# 10MHzRefOsc_2V1.net
KiCad netlist of a schematic drawn in EAGLE
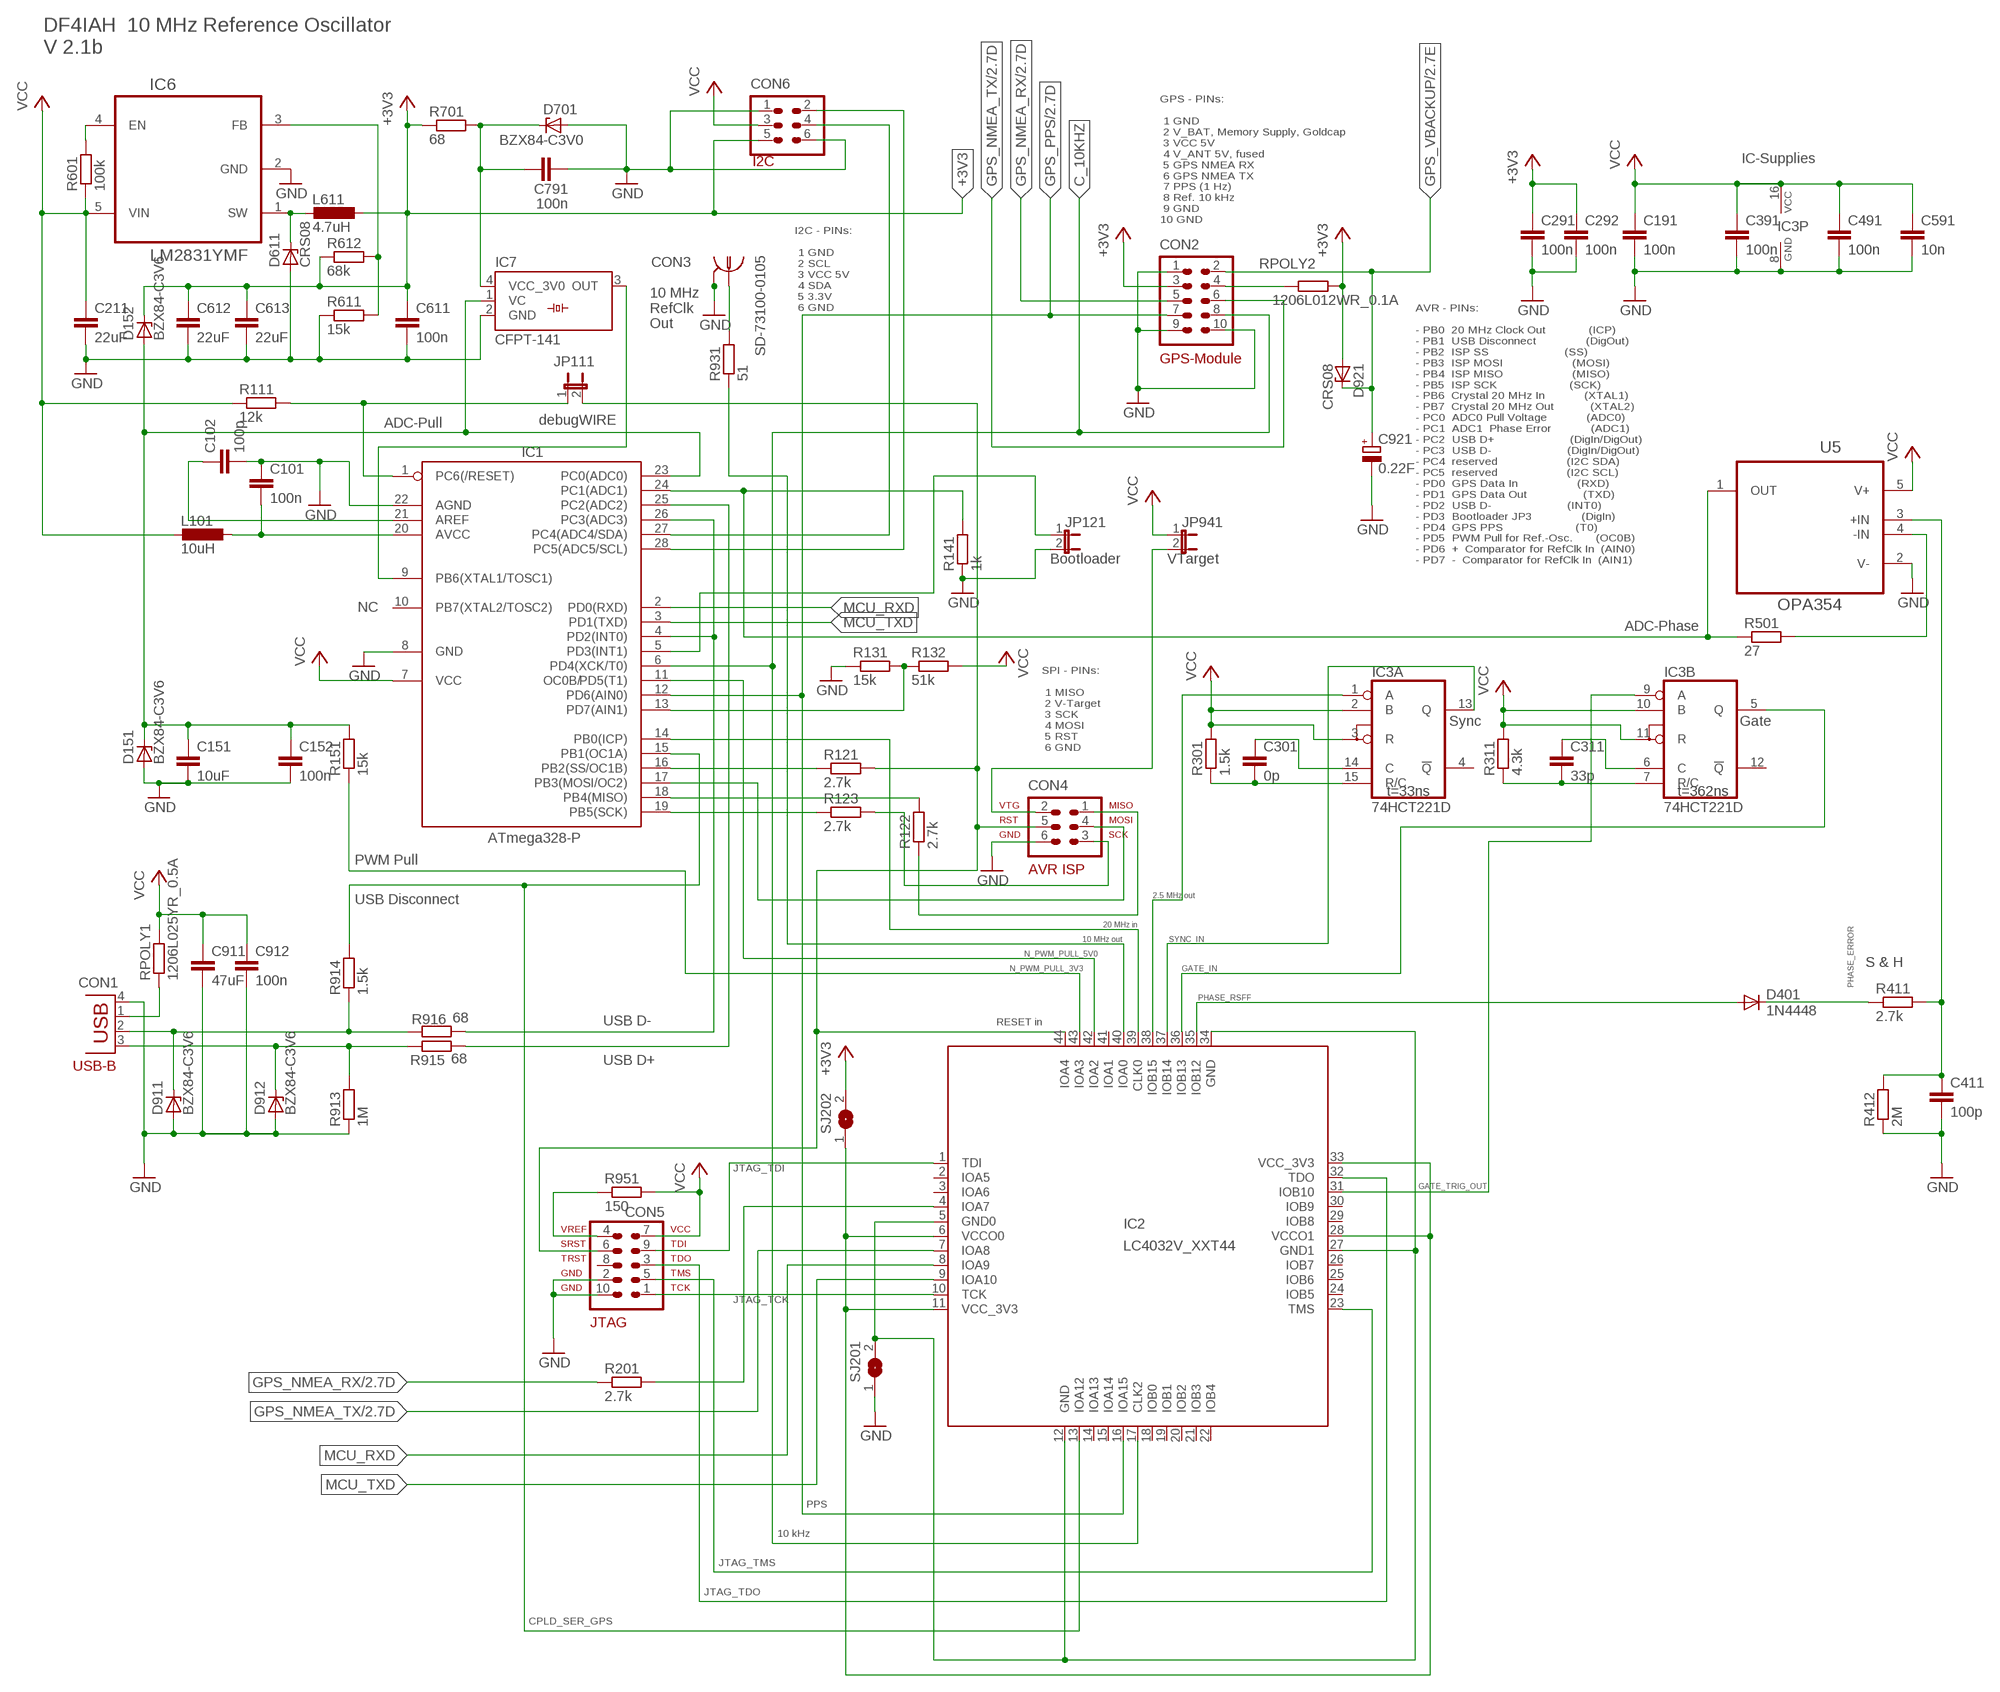
[diagram p0: schematic, sheet 1]
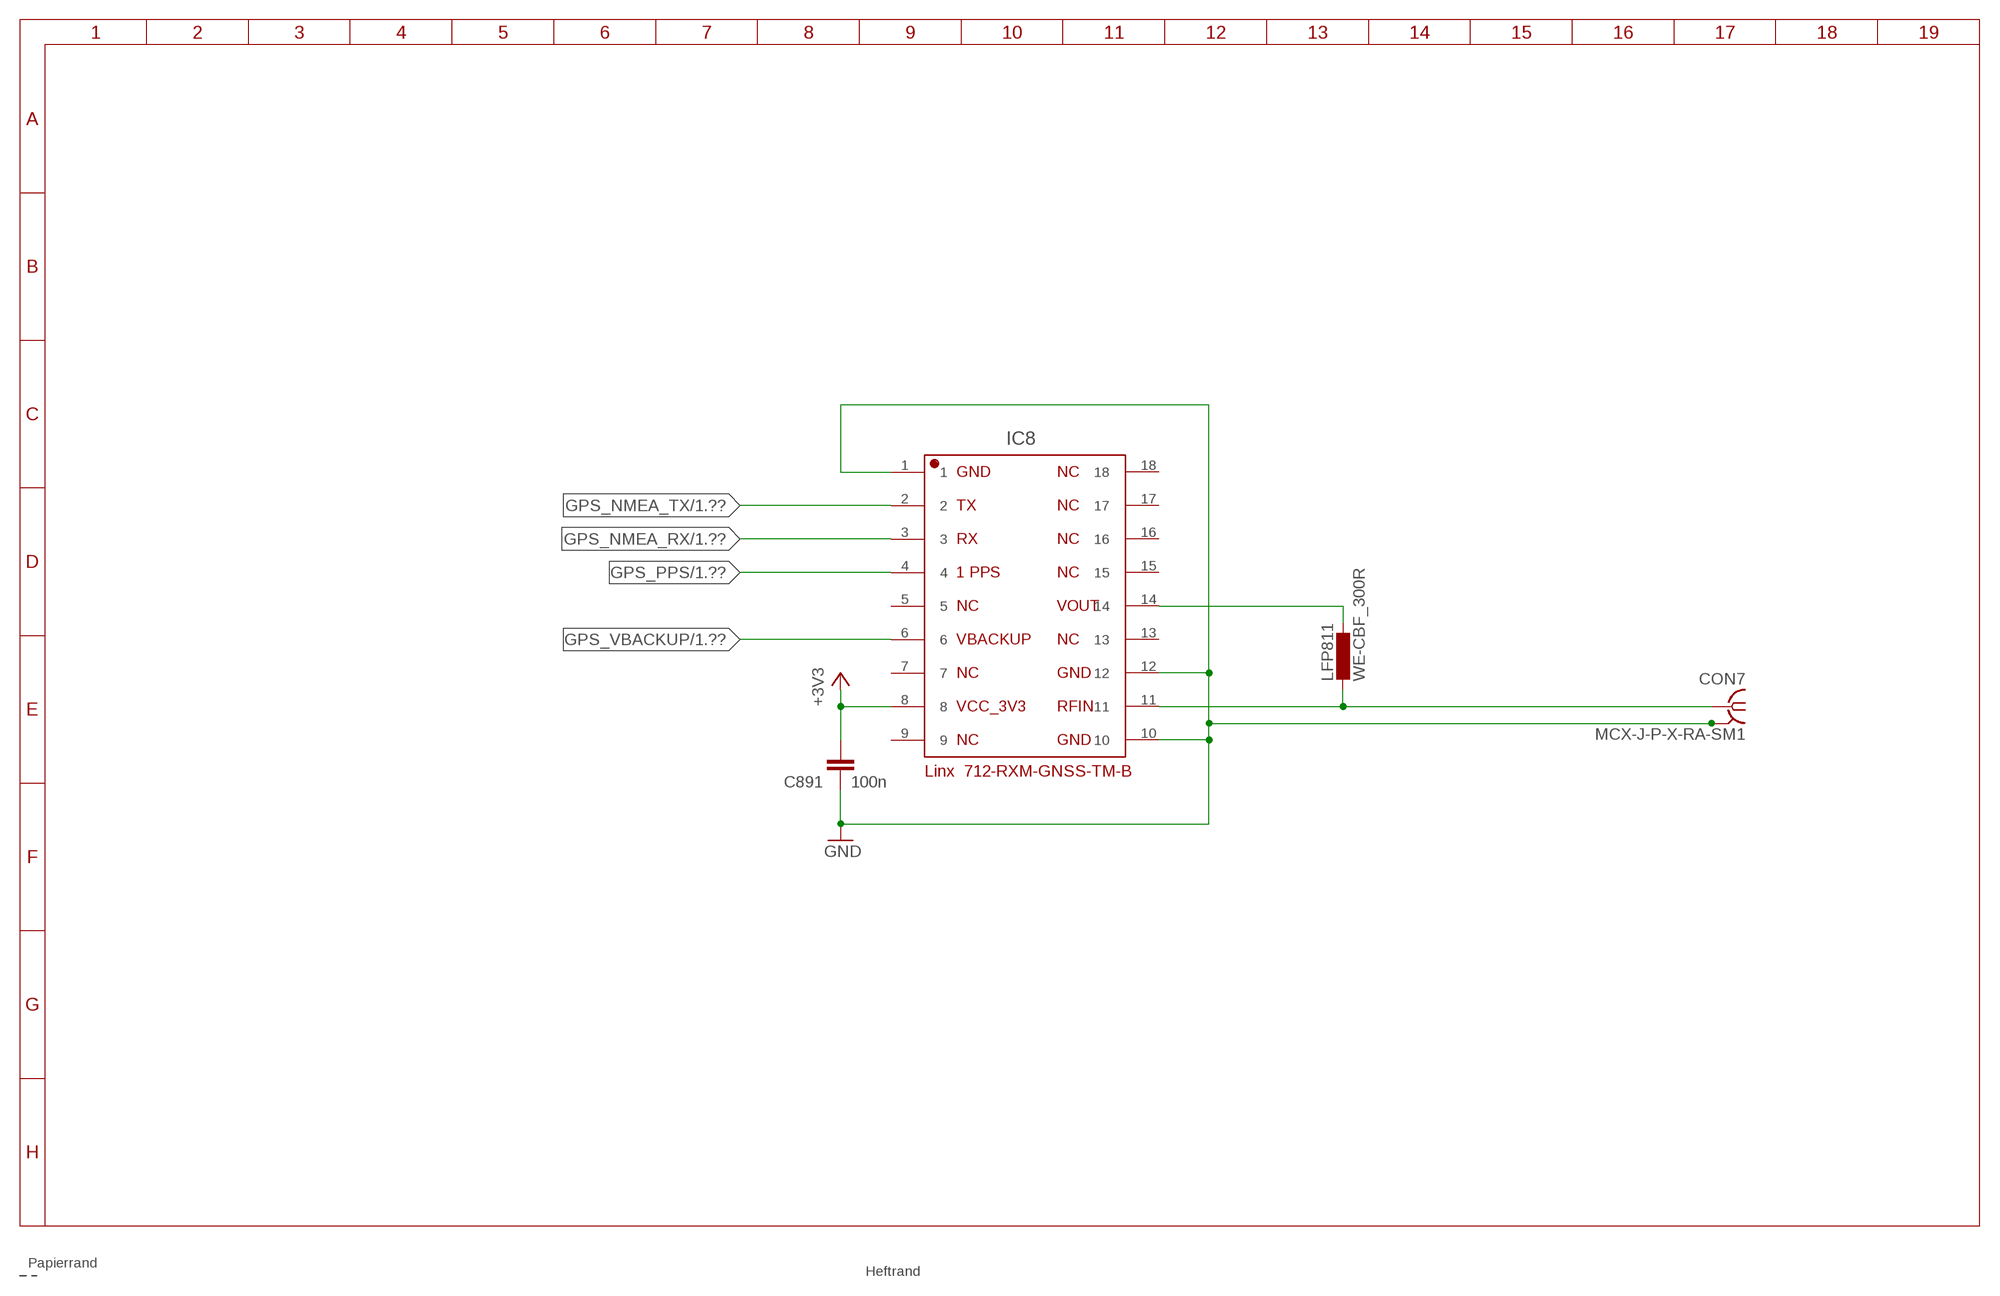
[diagram p1: schematic, sheet 2]
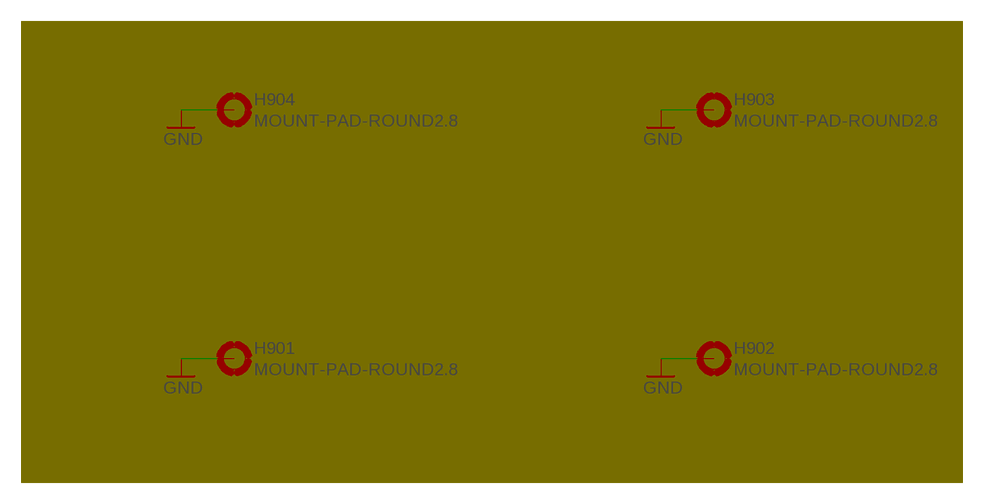
[diagram p2: schematic, sheet 3]

(export (version "E")
  (design (tool "Eeschema 10.0.6"))
  (components
    (comp (ref "C101")
      (value "100n")
      (footprint "eagle-import:C0805")
      (libsource (lib "eagle-import") (part "rcl_C-EUC0805"))
    )
    (comp (ref "C102")
      (value "100p")
      (footprint "eagle-import:C0805")
      (libsource (lib "eagle-import") (part "rcl_C-EUC0805"))
    )
    (comp (ref "C151")
      (value "10uF")
      (footprint "eagle-import:C0805")
      (libsource (lib "eagle-import") (part "rcl_C-EUC0805"))
    )
    (comp (ref "C152")
      (value "100n")
      (footprint "eagle-import:C0805")
      (libsource (lib "eagle-import") (part "rcl_C-EUC0805"))
    )
    (comp (ref "C191")
      (value "100n")
      (footprint "eagle-import:C0805")
      (libsource (lib "eagle-import") (part "rcl_C-EUC0805"))
    )
    (comp (ref "C211")
      (value "22uF")
      (footprint "eagle-import:C0805")
      (libsource (lib "eagle-import") (part "rcl_C-EUC0805"))
    )
    (comp (ref "C291")
      (value "100n")
      (footprint "eagle-import:C0805")
      (libsource (lib "eagle-import") (part "rcl_C-EUC0805"))
    )
    (comp (ref "C292")
      (value "100n")
      (footprint "eagle-import:C0805")
      (libsource (lib "eagle-import") (part "rcl_C-EUC0805"))
    )
    (comp (ref "C301")
      (value "0p")
      (footprint "eagle-import:C0805")
      (libsource (lib "eagle-import") (part "rcl_C-EUC0805"))
    )
    (comp (ref "C311")
      (value "33p")
      (footprint "eagle-import:C0805")
      (libsource (lib "eagle-import") (part "rcl_C-EUC0805"))
    )
    (comp (ref "C391")
      (value "100n")
      (footprint "eagle-import:C0805")
      (libsource (lib "eagle-import") (part "rcl_C-EUC0805"))
    )
    (comp (ref "C411")
      (value "100p")
      (footprint "eagle-import:C0805")
      (libsource (lib "eagle-import") (part "rcl_C-EUC0805"))
    )
    (comp (ref "C491")
      (value "100n")
      (footprint "eagle-import:C0805")
      (libsource (lib "eagle-import") (part "rcl_C-EUC0805"))
    )
    (comp (ref "C591")
      (value "10n")
      (footprint "eagle-import:C0805")
      (libsource (lib "eagle-import") (part "rcl_C-EUC0805"))
    )
    (comp (ref "C611")
      (value "100n")
      (footprint "eagle-import:C0805")
      (libsource (lib "eagle-import") (part "rcl_C-EUC0805"))
    )
    (comp (ref "C612")
      (value "22uF")
      (footprint "eagle-import:C0805")
      (libsource (lib "eagle-import") (part "rcl_C-EUC0805"))
    )
    (comp (ref "C613")
      (value "22uF")
      (footprint "eagle-import:C0805")
      (libsource (lib "eagle-import") (part "rcl_C-EUC0805"))
    )
    (comp (ref "C791")
      (value "100n")
      (footprint "eagle-import:C0805")
      (libsource (lib "eagle-import") (part "rcl_C-EUC0805"))
    )
    (comp (ref "C911")
      (value "47uF")
      (footprint "eagle-import:C0805")
      (libsource (lib "eagle-import") (part "rcl_C-EUC0805"))
    )
    (comp (ref "C912")
      (value "100n")
      (footprint "eagle-import:C0805")
      (libsource (lib "eagle-import") (part "rcl_C-EUC0805"))
    )
    (comp (ref "C921")
      (value "0.22F")
      (footprint "eagle-import:140CLH-1010")
      (libsource (lib "eagle-import") (part "CPOL-EU140CLH-1010"))
    )
    (comp (ref "CON1")
      (value "TYCO-AMP_USBUSB-B_SMT")
      (footprint "eagle-import:TYCO-AMP_USB-B_SMT")
      (fields (field (name "MF") "TYCO-AMP") (field (name "MPN") "1734346"))
      (libsource (lib "eagle-import") (part "TYCO-AMP_USBUSB-B_SMT"))
    )
    (comp (ref "CON2")
      (value "HEADER-2X5SMD")
      (footprint "eagle-import:2X5SMD")
      (libsource (lib "eagle-import") (part "HEADER-2X5SMD"))
    )
    (comp (ref "CON3")
      (value "SD-73100-0105")
      (footprint "eagle-import:MOLEX_BNC-JACK-50R_SD-73100-0105")
      (fields (field (name "MF") "MOLEX"))
      (libsource (lib "eagle-import") (part "MOLEX_BNC-JACK-50R_SD-73100-0105"))
    )
    (comp (ref "CON4")
      (value "AVR-ISP-6SMD")
      (footprint "eagle-import:2X3SMD")
      (libsource (lib "eagle-import") (part "AVR-ISP-6SMD"))
    )
    (comp (ref "CON5")
      (value "AVR-JTAG-10SMD")
      (footprint "eagle-import:2X5SMD")
      (libsource (lib "eagle-import") (part "AVR-JTAG-10SMD"))
    )
    (comp (ref "CON6")
      (value "HEADER-2X3SMD")
      (footprint "eagle-import:2X03SMD")
      (libsource (lib "eagle-import") (part "HEADER-2X3SMD"))
    )
    (comp (ref "D151")
      (value "BZX84-C3V6")
      (footprint "eagle-import:TO236")
      (libsource (lib "eagle-import") (part "BZX84CSMD"))
    )
    (comp (ref "D152")
      (value "BZX84-C3V6")
      (footprint "eagle-import:TO236")
      (libsource (lib "eagle-import") (part "BZX84CSMD"))
    )
    (comp (ref "D401")
      (value "1N4448")
      (footprint "eagle-import:SOD123")
      (libsource (lib "eagle-import") (part "DIODE-SOD123"))
    )
    (comp (ref "D611")
      (value "CRS08")
      (footprint "eagle-import:SOD80C")
      (libsource (lib "eagle-import") (part "ZENER-DIODESOD80C"))
    )
    (comp (ref "D701")
      (value "BZX84-C3V0")
      (footprint "eagle-import:TO236")
      (libsource (lib "eagle-import") (part "BZX84CSMD"))
    )
    (comp (ref "D911")
      (value "BZX84-C3V6")
      (footprint "eagle-import:TO236")
      (libsource (lib "eagle-import") (part "BZX84CSMD"))
    )
    (comp (ref "D912")
      (value "BZX84-C3V6")
      (footprint "eagle-import:TO236")
      (libsource (lib "eagle-import") (part "BZX84CSMD"))
    )
    (comp (ref "D921")
      (value "CRS08")
      (footprint "eagle-import:SOD80C")
      (libsource (lib "eagle-import") (part "ZENER-DIODESOD80C"))
    )
    (comp (ref "IC1")
      (value "ATmega328-P")
      (footprint "eagle-import:DIL28-3")
      (libsource (lib "eagle-import") (part "MEGA8-P"))
    )
    (comp (ref "IC2")
      (value "LC4032V_XXT44")
      (footprint "eagle-import:TQFP44")
      (libsource (lib "eagle-import") (part "LC4032V_XXT44"))
    )
    (comp (ref "IC3")
      (value "74HCT221D")
      (footprint "eagle-import:SO16")
      (libsource (lib "eagle-import") (part "74221DHCT"))
    )
    (comp (ref "IC6")
      (value "LM2831YMF")
      (footprint "eagle-import:SOT95P280X145-5N")
      (fields (field (name "MPN") "LM2831YMF/NOPB"))
      (libsource (lib "eagle-import") (part "LM2831YMF"))
    )
    (comp (ref "IC7")
      (value "CFPT-141")
      (footprint "eagle-import:CFPT-141")
      (fields (field (name "MF") "IQD-FREQUENCY-PRODUCTS") (field (name "MPN") "LFTVXO022175"))
      (libsource (lib "eagle-import") (part "CFPT-141"))
    )
    (comp (ref "JP111")
      (value "JP1E")
      (footprint "eagle-import:JP1")
      (libsource (lib "eagle-import") (part "JP1E"))
    )
    (comp (ref "JP121")
      (value "JP1E")
      (footprint "eagle-import:JP1")
      (libsource (lib "eagle-import") (part "JP1E"))
    )
    (comp (ref "JP941")
      (value "JP1E")
      (footprint "eagle-import:JP1")
      (libsource (lib "eagle-import") (part "JP1E"))
    )
    (comp (ref "L101")
      (value "10uH")
      (footprint "eagle-import:L1812")
      (libsource (lib "eagle-import") (part "rcl_L-EUL1812"))
    )
    (comp (ref "L611")
      (value "4.7uH")
      (footprint "eagle-import:L5650M")
      (libsource (lib "eagle-import") (part "rcl_L-EUL5650M"))
    )
    (comp (ref "R111")
      (value "12k")
      (footprint "eagle-import:R0805")
      (libsource (lib "eagle-import") (part "R-EU_R0805"))
    )
    (comp (ref "R121")
      (value "2.7k")
      (footprint "eagle-import:R0805")
      (libsource (lib "eagle-import") (part "R-EU_R0805"))
    )
    (comp (ref "R122")
      (value "2.7k")
      (footprint "eagle-import:R0805")
      (libsource (lib "eagle-import") (part "R-EU_R0805"))
    )
    (comp (ref "R123")
      (value "2.7k")
      (footprint "eagle-import:R0805")
      (libsource (lib "eagle-import") (part "R-EU_R0805"))
    )
    (comp (ref "R131")
      (value "15k")
      (footprint "eagle-import:R0805")
      (libsource (lib "eagle-import") (part "R-EU_R0805"))
    )
    (comp (ref "R132")
      (value "51k")
      (footprint "eagle-import:R0805")
      (libsource (lib "eagle-import") (part "R-EU_R0805"))
    )
    (comp (ref "R141")
      (value "1k")
      (footprint "eagle-import:R0805")
      (libsource (lib "eagle-import") (part "R-EU_R0805"))
    )
    (comp (ref "R151")
      (value "15k")
      (footprint "eagle-import:R0805")
      (libsource (lib "eagle-import") (part "R-EU_R0805"))
    )
    (comp (ref "R201")
      (value "2.7k")
      (footprint "eagle-import:R0805")
      (libsource (lib "eagle-import") (part "R-EU_R0805"))
    )
    (comp (ref "R301")
      (value "1.5k")
      (footprint "eagle-import:R0805")
      (libsource (lib "eagle-import") (part "R-EU_R0805"))
    )
    (comp (ref "R311")
      (value "4.3k")
      (footprint "eagle-import:R0805")
      (libsource (lib "eagle-import") (part "R-EU_R0805"))
    )
    (comp (ref "R411")
      (value "2.7k")
      (footprint "eagle-import:R0805")
      (libsource (lib "eagle-import") (part "R-EU_R0805"))
    )
    (comp (ref "R412")
      (value "2M")
      (footprint "eagle-import:R0805")
      (libsource (lib "eagle-import") (part "R-EU_R0805"))
    )
    (comp (ref "R501")
      (value "27")
      (footprint "eagle-import:R0805")
      (libsource (lib "eagle-import") (part "R-EU_R0805"))
    )
    (comp (ref "R601")
      (value "100k")
      (footprint "eagle-import:R0805")
      (libsource (lib "eagle-import") (part "R-EU_R0805"))
    )
    (comp (ref "R611")
      (value "15k")
      (footprint "eagle-import:R0805")
      (libsource (lib "eagle-import") (part "R-EU_R0805"))
    )
    (comp (ref "R612")
      (value "68k")
      (footprint "eagle-import:R0805")
      (libsource (lib "eagle-import") (part "R-EU_R0805"))
    )
    (comp (ref "R701")
      (value "68")
      (footprint "eagle-import:R0805")
      (libsource (lib "eagle-import") (part "R-EU_R0805"))
    )
    (comp (ref "R913")
      (value "1M")
      (footprint "eagle-import:R0805")
      (libsource (lib "eagle-import") (part "R-EU_R0805"))
    )
    (comp (ref "R914")
      (value "1.5k")
      (footprint "eagle-import:R0805")
      (libsource (lib "eagle-import") (part "R-EU_R0805"))
    )
    (comp (ref "R915")
      (value "68")
      (footprint "eagle-import:R0805")
      (libsource (lib "eagle-import") (part "R-EU_R0805"))
    )
    (comp (ref "R916")
      (value "68")
      (footprint "eagle-import:R0805")
      (libsource (lib "eagle-import") (part "R-EU_R0805"))
    )
    (comp (ref "R931")
      (value "51")
      (footprint "eagle-import:R0805")
      (libsource (lib "eagle-import") (part "R-EU_R0805"))
    )
    (comp (ref "R951")
      (value "150")
      (footprint "eagle-import:R0805")
      (libsource (lib "eagle-import") (part "R-EU_R0805"))
    )
    (comp (ref "RPOLY1")
      (value "1206L025YR_0.5A")
      (footprint "eagle-import:M1206")
      (libsource (lib "eagle-import") (part "R-EU_M1206"))
    )
    (comp (ref "RPOLY2")
      (value "1206L012WR_0.1A")
      (footprint "eagle-import:M1206")
      (libsource (lib "eagle-import") (part "R-EU_M1206"))
    )
    (comp (ref "SJ201")
      (value "SJ")
      (footprint "eagle-import:SJ")
      (libsource (lib "eagle-import") (part "SJ"))
    )
    (comp (ref "SJ202")
      (value "SJ")
      (footprint "eagle-import:SJ")
      (libsource (lib "eagle-import") (part "SJ"))
    )
    (comp (ref "U5")
      (value "OPA354")
      (footprint "eagle-import:SOT-23-5")
      (fields (field (name "MPN") "OPA354AIDBVT"))
      (libsource (lib "eagle-import") (part "OPA354"))
    )
    (comp (ref "C891")
      (value "100n")
      (footprint "eagle-import:C0805")
      (libsource (lib "eagle-import") (part "C-EUC0805"))
    )
    (comp (ref "CON7")
      (value "MCX-J-P-X-RA-SM1")
      (footprint "eagle-import:MCX-J-P-X-RA-SM1")
      (libsource (lib "eagle-import") (part "MCX-J-P-X-RA-SM1"))
    )
    (comp (ref "IC8")
      (value "712-RXM-GNSS-TM-B")
      (footprint "eagle-import:712-RXM-GNSS-TM-B")
      (libsource (lib "eagle-import") (part "712-RXM-GNSS-TM-B"))
    )
    (comp (ref "LFP811")
      (value "WE-CBF_300R")
      (footprint "eagle-import:L3216C")
      (libsource (lib "eagle-import") (part "L-EUL3216C"))
    )
    (comp (ref "H901")
      (value "MOUNT-PAD-ROUND2.8")
      (footprint "eagle-import:2,8-PAD")
      (libsource (lib "eagle-import") (part "MOUNT-PAD-ROUND2.8"))
    )
    (comp (ref "H902")
      (value "MOUNT-PAD-ROUND2.8")
      (footprint "eagle-import:2,8-PAD")
      (libsource (lib "eagle-import") (part "MOUNT-PAD-ROUND2.8"))
    )
    (comp (ref "H903")
      (value "MOUNT-PAD-ROUND2.8")
      (footprint "eagle-import:2,8-PAD")
      (libsource (lib "eagle-import") (part "MOUNT-PAD-ROUND2.8"))
    )
    (comp (ref "H904")
      (value "MOUNT-PAD-ROUND2.8")
      (footprint "eagle-import:2,8-PAD")
      (libsource (lib "eagle-import") (part "MOUNT-PAD-ROUND2.8"))
    )
  )
  (nets
    (net (code "1") (name "+3V3") (class "Default")
      (node (ref "C291") (pin "1") (pinfunction "1_1") (pintype "passive"))
      (node (ref "C292") (pin "1") (pinfunction "1_1") (pintype "passive"))
      (node (ref "C611") (pin "1") (pinfunction "1_1") (pintype "passive"))
      (node (ref "C612") (pin "1") (pinfunction "1_1") (pintype "passive"))
      (node (ref "C613") (pin "1") (pinfunction "1_1") (pintype "passive"))
      (node (ref "C891") (pin "1") (pinfunction "1_1") (pintype "passive"))
      (node (ref "CON2") (pin "3") (pinfunction "3_3") (pintype "passive"))
      (node (ref "CON6") (pin "5") (pinfunction "5_5") (pintype "passive"))
      (node (ref "D152") (pin "C") (pinfunction "C_C") (pintype "passive"))
      (node (ref "D921") (pin "A") (pinfunction "A_A") (pintype "passive"))
      (node (ref "IC8") (pin "8") (pinfunction "8_8") (pintype "power_in"))
      (node (ref "L611") (pin "1") (pinfunction "1_1") (pintype "passive"))
      (node (ref "R612") (pin "1") (pinfunction "1_1") (pintype "passive"))
      (node (ref "R701") (pin "1") (pinfunction "1_1") (pintype "passive"))
      (node (ref "RPOLY2") (pin "2") (pinfunction "2_2") (pintype "passive"))
      (node (ref "SJ202") (pin "2") (pinfunction "2_2") (pintype "passive"))
    )
    (net (code "2") (name "C_10KHZ") (class "Default")
      (node (ref "CON2") (pin "8") (pinfunction "8_8") (pintype "passive"))
      (node (ref "IC1") (pin "6") (pinfunction "PD4(XCK/T0)_6") (pintype "bidirectional"))
      (node (ref "IC2") (pin "17") (pinfunction "CLK2_17") (pintype "input"))
    )
    (net (code "3") (name "GATE_IN") (class "Default")
      (node (ref "IC2") (pin "36") (pinfunction "IOB13_36") (pintype "bidirectional"))
      (node (ref "IC3") (pin "5") (pinfunction "Q_5") (pintype "output"))
    )
    (net (code "4") (name "GATE_TRIG_OUT") (class "Default")
      (node (ref "IC2") (pin "31") (pinfunction "IOB10_31") (pintype "bidirectional"))
      (node (ref "IC3") (pin "9") (pinfunction "A_9") (pintype "input"))
    )
    (net (code "5") (name "GND") (class "Default")
      (node (ref "C101") (pin "1") (pinfunction "1_1") (pintype "passive"))
      (node (ref "C102") (pin "2") (pinfunction "2_2") (pintype "passive"))
      (node (ref "C151") (pin "2") (pinfunction "2_2") (pintype "passive"))
      (node (ref "C152") (pin "2") (pinfunction "2_2") (pintype "passive"))
      (node (ref "C191") (pin "2") (pinfunction "2_2") (pintype "passive"))
      (node (ref "C211") (pin "2") (pinfunction "2_2") (pintype "passive"))
      (node (ref "C291") (pin "2") (pinfunction "2_2") (pintype "passive"))
      (node (ref "C292") (pin "2") (pinfunction "2_2") (pintype "passive"))
      (node (ref "C391") (pin "2") (pinfunction "2_2") (pintype "passive"))
      (node (ref "C411") (pin "2") (pinfunction "2_2") (pintype "passive"))
      (node (ref "C491") (pin "2") (pinfunction "2_2") (pintype "passive"))
      (node (ref "C591") (pin "2") (pinfunction "2_2") (pintype "passive"))
      (node (ref "C611") (pin "2") (pinfunction "2_2") (pintype "passive"))
      (node (ref "C612") (pin "2") (pinfunction "2_2") (pintype "passive"))
      (node (ref "C613") (pin "2") (pinfunction "2_2") (pintype "passive"))
      (node (ref "C791") (pin "2") (pinfunction "2_2") (pintype "passive"))
      (node (ref "C891") (pin "2") (pinfunction "2_2") (pintype "passive"))
      (node (ref "C911") (pin "2") (pinfunction "2_2") (pintype "passive"))
      (node (ref "C912") (pin "2") (pinfunction "2_2") (pintype "passive"))
      (node (ref "C921") (pin "-") (pinfunction "-_-") (pintype "passive"))
      (node (ref "CON1") (pin "4") (pinfunction "GND_4") (pintype "bidirectional"))
      (node (ref "CON2") (pin "1") (pinfunction "1_1") (pintype "passive"))
      (node (ref "CON2") (pin "10") (pinfunction "10_10") (pintype "passive"))
      (node (ref "CON2") (pin "9") (pinfunction "9_9") (pintype "passive"))
      (node (ref "CON3") (pin "2") (pinfunction "2_2") (pintype "passive"))
      (node (ref "CON3") (pin "3") (pinfunction "3_3") (pintype "passive"))
      (node (ref "CON4") (pin "6") (pinfunction "6_6") (pintype "passive"))
      (node (ref "CON5") (pin "10") (pinfunction "10_10") (pintype "passive"))
      (node (ref "CON5") (pin "2") (pinfunction "2_2") (pintype "passive"))
      (node (ref "CON6") (pin "1") (pinfunction "1_1") (pintype "passive"))
      (node (ref "CON6") (pin "6") (pinfunction "6_6") (pintype "passive"))
      (node (ref "CON7") (pin "2") (pinfunction "2_2") (pintype "passive"))
      (node (ref "CON7") (pin "3") (pinfunction "3_3") (pintype "passive"))
      (node (ref "CON7") (pin "4") (pinfunction "4_4") (pintype "passive"))
      (node (ref "CON7") (pin "5") (pinfunction "5_5") (pintype "passive"))
      (node (ref "D151") (pin "A") (pinfunction "A_A") (pintype "passive"))
      (node (ref "D611") (pin "A") (pinfunction "A_A") (pintype "passive"))
      (node (ref "D701") (pin "A") (pinfunction "A_A") (pintype "passive"))
      (node (ref "D911") (pin "A") (pinfunction "A_A") (pintype "passive"))
      (node (ref "D912") (pin "A") (pinfunction "A_A") (pintype "passive"))
      (node (ref "H901") (pin "B2,8") (pinfunction "MOUNT_B2,8") (pintype "passive"))
      (node (ref "H902") (pin "B2,8") (pinfunction "MOUNT_B2,8") (pintype "passive"))
      (node (ref "H903") (pin "B2,8") (pinfunction "MOUNT_B2,8") (pintype "passive"))
      (node (ref "H904") (pin "B2,8") (pinfunction "MOUNT_B2,8") (pintype "passive"))
      (node (ref "IC1") (pin "22") (pinfunction "AGND_22") (pintype "bidirectional"))
      (node (ref "IC1") (pin "8") (pinfunction "GND_8") (pintype "bidirectional"))
      (node (ref "IC3") (pin "8") (pinfunction "GND_8") (pintype "power_in"))
      (node (ref "IC6") (pin "2") (pinfunction "GND_2") (pintype "passive"))
      (node (ref "IC7") (pin "2") (pinfunction "GND_2") (pintype "power_in"))
      (node (ref "IC8") (pin "1") (pinfunction "1_1") (pintype "power_in"))
      (node (ref "IC8") (pin "10") (pinfunction "10_10") (pintype "power_in"))
      (node (ref "IC8") (pin "12") (pinfunction "12_12") (pintype "power_in"))
      (node (ref "JP121") (pin "2") (pinfunction "2_2") (pintype "passive"))
      (node (ref "R131") (pin "1") (pinfunction "1_1") (pintype "passive"))
      (node (ref "R141") (pin "1") (pinfunction "1_1") (pintype "passive"))
      (node (ref "R412") (pin "1") (pinfunction "1_1") (pintype "passive"))
      (node (ref "R611") (pin "1") (pinfunction "1_1") (pintype "passive"))
      (node (ref "R913") (pin "1") (pinfunction "1_1") (pintype "passive"))
      (node (ref "SJ201") (pin "1") (pinfunction "1_1") (pintype "passive"))
      (node (ref "U5") (pin "2") (pinfunction "V-_2") (pintype "power_in"))
    )
    (net (code "6") (name "GPS_NMEA_RX") (class "Default")
      (node (ref "CON2") (pin "5") (pinfunction "5_5") (pintype "passive"))
      (node (ref "IC8") (pin "3") (pinfunction "3_3") (pintype "output"))
      (node (ref "R201") (pin "1") (pinfunction "1_1") (pintype "passive"))
    )
    (net (code "7") (name "GPS_NMEA_TX") (class "Default")
      (node (ref "CON2") (pin "6") (pinfunction "6_6") (pintype "passive"))
      (node (ref "IC2") (pin "7") (pinfunction "IOA8_7") (pintype "bidirectional"))
      (node (ref "IC8") (pin "2") (pinfunction "2_2") (pintype "input"))
    )
    (net (code "8") (name "GPS_PPS") (class "Default")
      (node (ref "CON2") (pin "7") (pinfunction "7_7") (pintype "passive"))
      (node (ref "IC1") (pin "12") (pinfunction "PD6(AIN0)_12") (pintype "bidirectional"))
      (node (ref "IC2") (pin "16") (pinfunction "IOA15_16") (pintype "bidirectional"))
      (node (ref "IC8") (pin "4") (pinfunction "4_4") (pintype "output"))
    )
    (net (code "9") (name "GPS_VBACKUP") (class "Default")
      (node (ref "C921") (pin "+") (pinfunction "+_+") (pintype "passive"))
      (node (ref "CON2") (pin "2") (pinfunction "2_2") (pintype "passive"))
      (node (ref "D921") (pin "C") (pinfunction "C_C") (pintype "passive"))
      (node (ref "IC8") (pin "6") (pinfunction "6_6") (pintype "power_in"))
    )
    (net (code "10") (name "MCU_RXD") (class "Default")
      (node (ref "IC1") (pin "2") (pinfunction "PD0(RXD)_2") (pintype "bidirectional"))
      (node (ref "IC2") (pin "8") (pinfunction "IOA9_8") (pintype "bidirectional"))
    )
    (net (code "11") (name "MCU_TXD") (class "Default")
      (node (ref "IC1") (pin "3") (pinfunction "PD1(TXD)_3") (pintype "bidirectional"))
      (node (ref "IC2") (pin "9") (pinfunction "IOA10_9") (pintype "bidirectional"))
    )
    (net (code "12") (name "N_PWM_PULL_3V3") (class "Default")
      (node (ref "IC2") (pin "43") (pinfunction "IOA3_43") (pintype "bidirectional"))
      (node (ref "R151") (pin "1") (pinfunction "1_1") (pintype "passive"))
    )
    (net (code "13") (name "N_PWM_PULL_5V0") (class "Default")
      (node (ref "IC1") (pin "11") (pinfunction "PD5(T1)_11") (pintype "bidirectional"))
      (node (ref "IC2") (pin "42") (pinfunction "IOA2_42") (pintype "bidirectional"))
    )
    (net (code "14") (name "Net-(CON1-D+)") (class "Default")
      (node (ref "CON1") (pin "3") (pinfunction "D+_3") (pintype "bidirectional"))
      (node (ref "D912") (pin "C") (pinfunction "C_C") (pintype "passive"))
      (node (ref "R913") (pin "2") (pinfunction "2_2") (pintype "passive"))
      (node (ref "R915") (pin "1") (pinfunction "1_1") (pintype "passive"))
    )
    (net (code "15") (name "Net-(CON1-D-)") (class "Default")
      (node (ref "CON1") (pin "2") (pinfunction "D-_2") (pintype "bidirectional"))
      (node (ref "D911") (pin "C") (pinfunction "C_C") (pintype "passive"))
      (node (ref "R914") (pin "1") (pinfunction "1_1") (pintype "passive"))
      (node (ref "R916") (pin "1") (pinfunction "1_1") (pintype "passive"))
    )
    (net (code "16") (name "Net-(CON1-VBUS)") (class "Default")
      (node (ref "CON1") (pin "1") (pinfunction "VBUS_1") (pintype "bidirectional"))
      (node (ref "RPOLY1") (pin "1") (pinfunction "1_1") (pintype "passive"))
    )
    (net (code "17") (name "Net-(CON2-Pad4)") (class "Default")
      (node (ref "CON2") (pin "4") (pinfunction "4_4") (pintype "passive"))
      (node (ref "RPOLY2") (pin "1") (pinfunction "1_1") (pintype "passive"))
    )
    (net (code "18") (name "Net-(CON3-Pad1)") (class "Default")
      (node (ref "CON3") (pin "1") (pinfunction "1_1") (pintype "passive"))
      (node (ref "R931") (pin "2") (pinfunction "2_2") (pintype "passive"))
    )
    (net (code "19") (name "Net-(CON4-Pad1)") (class "Default")
      (node (ref "CON4") (pin "1") (pinfunction "1_1") (pintype "passive"))
      (node (ref "R122") (pin "1") (pinfunction "1_1") (pintype "passive"))
    )
    (net (code "20") (name "Net-(CON4-Pad2)") (class "Default")
      (node (ref "CON4") (pin "2") (pinfunction "2_2") (pintype "passive"))
      (node (ref "JP941") (pin "2") (pinfunction "2_2") (pintype "passive"))
    )
    (net (code "21") (name "Net-(CON4-Pad3)") (class "Default")
      (node (ref "CON4") (pin "3") (pinfunction "3_3") (pintype "passive"))
      (node (ref "R123") (pin "2") (pinfunction "2_2") (pintype "passive"))
    )
    (net (code "22") (name "Net-(CON5-Pad4)") (class "Default")
      (node (ref "CON5") (pin "4") (pinfunction "4_4") (pintype "passive"))
      (node (ref "R951") (pin "1") (pinfunction "1_1") (pintype "passive"))
    )
    (net (code "23") (name "Net-(CON7-Pad1)") (class "Default")
      (node (ref "CON7") (pin "1") (pinfunction "1_1") (pintype "passive"))
      (node (ref "IC8") (pin "11") (pinfunction "11_11") (pintype "input"))
      (node (ref "LFP811") (pin "2") (pinfunction "2_2") (pintype "passive"))
    )
    (net (code "24") (name "Net-(IC1-AREF)") (class "Default")
      (node (ref "C102") (pin "1") (pinfunction "1_1") (pintype "passive"))
      (node (ref "IC1") (pin "21") (pinfunction "AREF_21") (pintype "bidirectional"))
    )
    (net (code "25") (name "Net-(IC1-AVCC)") (class "Default")
      (node (ref "C101") (pin "2") (pinfunction "2_2") (pintype "passive"))
      (node (ref "IC1") (pin "20") (pinfunction "AVCC_20") (pintype "bidirectional"))
      (node (ref "L101") (pin "1") (pinfunction "1_1") (pintype "passive"))
    )
    (net (code "26") (name "Net-(IC1-PB0(ICP))") (class "Default")
      (node (ref "IC1") (pin "14") (pinfunction "PB0(ICP)_14") (pintype "bidirectional"))
      (node (ref "IC2") (pin "39") (pinfunction "CLK0_39") (pintype "input"))
    )
    (net (code "27") (name "Net-(IC1-PB1(OC1A))") (class "Default")
      (node (ref "IC1") (pin "15") (pinfunction "PB1(OC1A)_15") (pintype "bidirectional"))
      (node (ref "IC2") (pin "13") (pinfunction "IOA12_13") (pintype "bidirectional"))
      (node (ref "R914") (pin "2") (pinfunction "2_2") (pintype "passive"))
    )
    (net (code "28") (name "Net-(IC1-PB2(SS{slash}OC1B))") (class "Default")
      (node (ref "IC1") (pin "16") (pinfunction "PB2(SS/OC1B)_16") (pintype "bidirectional"))
      (node (ref "R121") (pin "1") (pinfunction "1_1") (pintype "passive"))
    )
    (net (code "29") (name "Net-(IC1-PB3(MOSI{slash}OC2))") (class "Default")
      (node (ref "CON4") (pin "4") (pinfunction "4_4") (pintype "passive"))
      (node (ref "IC1") (pin "17") (pinfunction "PB3(MOSI/OC2)_17") (pintype "bidirectional"))
    )
    (net (code "30") (name "Net-(IC1-PB4(MISO))") (class "Default")
      (node (ref "IC1") (pin "18") (pinfunction "PB4(MISO)_18") (pintype "bidirectional"))
      (node (ref "R122") (pin "2") (pinfunction "2_2") (pintype "passive"))
    )
    (net (code "31") (name "Net-(IC1-PB5(SCK))") (class "Default")
      (node (ref "IC1") (pin "19") (pinfunction "PB5(SCK)_19") (pintype "bidirectional"))
      (node (ref "R123") (pin "1") (pinfunction "1_1") (pintype "passive"))
    )
    (net (code "32") (name "Net-(IC1-PB6(XTAL1{slash}TOSC1))") (class "Default")
      (node (ref "IC1") (pin "9") (pinfunction "PB6(XTAL1/TOSC1)_9") (pintype "bidirectional"))
      (node (ref "IC7") (pin "3") (pinfunction "OUT_3") (pintype "output"))
    )
    (net (code "33") (name "Net-(IC1-PC0(ADC0))") (class "Default")
      (node (ref "C151") (pin "1") (pinfunction "1_1") (pintype "passive"))
      (node (ref "C152") (pin "1") (pinfunction "1_1") (pintype "passive"))
      (node (ref "D151") (pin "C") (pinfunction "C_C") (pintype "passive"))
      (node (ref "D152") (pin "A") (pinfunction "A_A") (pintype "passive"))
      (node (ref "IC1") (pin "23") (pinfunction "PC0(ADC0)_23") (pintype "bidirectional"))
      (node (ref "IC7") (pin "1") (pinfunction "VC_1") (pintype "input"))
      (node (ref "R151") (pin "2") (pinfunction "2_2") (pintype "passive"))
    )
    (net (code "34") (name "Net-(IC1-PC1(ADC1))") (class "Default")
      (node (ref "IC1") (pin "24") (pinfunction "PC1(ADC1)_24") (pintype "bidirectional"))
      (node (ref "R141") (pin "2") (pinfunction "2_2") (pintype "passive"))
      (node (ref "R501") (pin "1") (pinfunction "1_1") (pintype "passive"))
      (node (ref "U5") (pin "1") (pinfunction "OUT_1") (pintype "output"))
    )
    (net (code "35") (name "Net-(IC1-PC2(ADC2))") (class "Default")
      (node (ref "IC1") (pin "25") (pinfunction "PC2(ADC2)_25") (pintype "bidirectional"))
      (node (ref "R915") (pin "2") (pinfunction "2_2") (pintype "passive"))
    )
    (net (code "36") (name "Net-(IC1-PC3(ADC3))") (class "Default")
      (node (ref "IC1") (pin "26") (pinfunction "PC3(ADC3)_26") (pintype "bidirectional"))
      (node (ref "IC1") (pin "4") (pinfunction "PD2(INT0)_4") (pintype "bidirectional"))
      (node (ref "R916") (pin "2") (pinfunction "2_2") (pintype "passive"))
    )
    (net (code "37") (name "Net-(IC1-PC4(ADC4{slash}SDA))") (class "Default")
      (node (ref "CON6") (pin "4") (pinfunction "4_4") (pintype "passive"))
      (node (ref "IC1") (pin "27") (pinfunction "PC4(ADC4/SDA)_27") (pintype "bidirectional"))
    )
    (net (code "38") (name "Net-(IC1-PC5(ADC5{slash}SCL))") (class "Default")
      (node (ref "CON6") (pin "2") (pinfunction "2_2") (pintype "passive"))
      (node (ref "IC1") (pin "28") (pinfunction "PC5(ADC5/SCL)_28") (pintype "bidirectional"))
    )
    (net (code "39") (name "Net-(IC1-PC6({slash}RESET))") (class "Default")
      (node (ref "IC1") (pin "1") (pinfunction "PC6(/RESET)_1") (pintype "bidirectional"))
      (node (ref "JP111") (pin "1") (pinfunction "1_1") (pintype "passive"))
      (node (ref "R111") (pin "2") (pinfunction "2_2") (pintype "passive"))
    )
    (net (code "40") (name "Net-(IC1-PD3(INT1))") (class "Default")
      (node (ref "IC1") (pin "5") (pinfunction "PD3(INT1)_5") (pintype "bidirectional"))
      (node (ref "JP121") (pin "1") (pinfunction "1_1") (pintype "passive"))
    )
    (net (code "41") (name "Net-(IC1-PD7(AIN1))") (class "Default")
      (node (ref "IC1") (pin "13") (pinfunction "PD7(AIN1)_13") (pintype "bidirectional"))
      (node (ref "R131") (pin "2") (pinfunction "2_2") (pintype "passive"))
      (node (ref "R132") (pin "1") (pinfunction "1_1") (pintype "passive"))
    )
    (net (code "42") (name "Net-(IC2-GND0)") (class "Default")
      (node (ref "IC2") (pin "12") (pinfunction "GND_12") (pintype "power_in"))
      (node (ref "IC2") (pin "27") (pinfunction "GND1_27") (pintype "power_in"))
      (node (ref "IC2") (pin "34") (pinfunction "GND_34") (pintype "power_in"))
      (node (ref "IC2") (pin "5") (pinfunction "GND0_5") (pintype "power_in"))
      (node (ref "SJ201") (pin "2") (pinfunction "2_2") (pintype "passive"))
    )
    (net (code "43") (name "Net-(IC2-IOA0)") (class "Default")
      (node (ref "IC2") (pin "40") (pinfunction "IOA0_40") (pintype "bidirectional"))
      (node (ref "R931") (pin "1") (pinfunction "1_1") (pintype "passive"))
    )
    (net (code "44") (name "Net-(IC2-IOA4)") (class "Default")
      (node (ref "CON4") (pin "5") (pinfunction "5_5") (pintype "passive"))
      (node (ref "CON5") (pin "6") (pinfunction "6_6") (pintype "passive"))
      (node (ref "IC2") (pin "44") (pinfunction "IOA4_44") (pintype "bidirectional"))
      (node (ref "JP111") (pin "2") (pinfunction "2_2") (pintype "passive"))
      (node (ref "R121") (pin "2") (pinfunction "2_2") (pintype "passive"))
    )
    (net (code "45") (name "Net-(IC2-IOA7)") (class "Default")
      (node (ref "IC2") (pin "4") (pinfunction "IOA7_4") (pintype "bidirectional"))
      (node (ref "R201") (pin "2") (pinfunction "2_2") (pintype "passive"))
    )
    (net (code "46") (name "Net-(IC2-IOB15)") (class "Default")
      (node (ref "IC2") (pin "38") (pinfunction "IOB15_38") (pintype "bidirectional"))
      (node (ref "IC3") (pin "1") (pinfunction "A_1") (pintype "input"))
    )
    (net (code "47") (name "Net-(IC2-TCK)") (class "Default")
      (node (ref "CON5") (pin "1") (pinfunction "1_1") (pintype "passive"))
      (node (ref "IC2") (pin "10") (pinfunction "TCK_10") (pintype "input"))
    )
    (net (code "48") (name "Net-(IC2-TDI)") (class "Default")
      (node (ref "CON5") (pin "9") (pinfunction "9_9") (pintype "passive"))
      (node (ref "IC2") (pin "1") (pinfunction "TDI_1") (pintype "input"))
    )
    (net (code "49") (name "Net-(IC2-TDO)") (class "Default")
      (node (ref "CON5") (pin "3") (pinfunction "3_3") (pintype "passive"))
      (node (ref "IC2") (pin "32") (pinfunction "TDO_32") (pintype "output"))
    )
    (net (code "50") (name "Net-(IC2-TMS)") (class "Default")
      (node (ref "CON5") (pin "5") (pinfunction "5_5") (pintype "passive"))
      (node (ref "IC2") (pin "23") (pinfunction "TMS_23") (pintype "input"))
    )
    (net (code "51") (name "Net-(IC2-VCCO0)") (class "Default")
      (node (ref "IC2") (pin "11") (pinfunction "VCC_3V3_11") (pintype "power_in"))
      (node (ref "IC2") (pin "28") (pinfunction "VCCO1_28") (pintype "power_in"))
      (node (ref "IC2") (pin "33") (pinfunction "VCC_3V3_33") (pintype "power_in"))
      (node (ref "IC2") (pin "6") (pinfunction "VCCO0_6") (pintype "power_in"))
      (node (ref "SJ202") (pin "1") (pinfunction "1_1") (pintype "passive"))
    )
    (net (code "52") (name "Net-(IC3A-C)") (class "Default")
      (node (ref "C301") (pin "1") (pinfunction "1_1") (pintype "passive"))
      (node (ref "IC3") (pin "14") (pinfunction "C_14") (pintype "input"))
    )
    (net (code "53") (name "Net-(IC3A-R{slash}C)") (class "Default")
      (node (ref "C301") (pin "2") (pinfunction "2_2") (pintype "passive"))
      (node (ref "IC3") (pin "15") (pinfunction "R/C_15") (pintype "input"))
      (node (ref "R301") (pin "1") (pinfunction "1_1") (pintype "passive"))
    )
    (net (code "54") (name "Net-(IC3B-C)") (class "Default")
      (node (ref "C311") (pin "1") (pinfunction "1_1") (pintype "passive"))
      (node (ref "IC3") (pin "6") (pinfunction "C_6") (pintype "input"))
    )
    (net (code "55") (name "Net-(IC3B-R{slash}C)") (class "Default")
      (node (ref "C311") (pin "2") (pinfunction "2_2") (pintype "passive"))
      (node (ref "IC3") (pin "7") (pinfunction "R/C_7") (pintype "input"))
      (node (ref "R311") (pin "1") (pinfunction "1_1") (pintype "passive"))
    )
    (net (code "56") (name "Net-(IC6-EN)") (class "Default")
      (node (ref "IC6") (pin "4") (pinfunction "EN_4") (pintype "input"))
      (node (ref "R601") (pin "2") (pinfunction "2_2") (pintype "passive"))
    )
    (net (code "57") (name "Net-(IC6-FB)") (class "Default")
      (node (ref "IC6") (pin "3") (pinfunction "FB_3") (pintype "input"))
      (node (ref "R611") (pin "2") (pinfunction "2_2") (pintype "passive"))
      (node (ref "R612") (pin "2") (pinfunction "2_2") (pintype "passive"))
    )
    (net (code "58") (name "Net-(IC6-SW)") (class "Default")
      (node (ref "D611") (pin "C") (pinfunction "C_C") (pintype "passive"))
      (node (ref "IC6") (pin "1") (pinfunction "SW_1") (pintype "output"))
      (node (ref "L611") (pin "2") (pinfunction "2_2") (pintype "passive"))
    )
    (net (code "59") (name "Net-(IC7-VCC_3V0)") (class "Default")
      (node (ref "C791") (pin "1") (pinfunction "1_1") (pintype "passive"))
      (node (ref "D701") (pin "C") (pinfunction "C_C") (pintype "passive"))
      (node (ref "IC7") (pin "4") (pinfunction "VCC_3V0_4") (pintype "power_in"))
      (node (ref "R701") (pin "2") (pinfunction "2_2") (pintype "passive"))
    )
    (net (code "60") (name "Net-(IC8-Pad14)") (class "Default")
      (node (ref "IC8") (pin "14") (pinfunction "14_14") (pintype "power_in"))
      (node (ref "LFP811") (pin "1") (pinfunction "1_1") (pintype "passive"))
    )
    (net (code "61") (name "Net-(U5-+IN)") (class "Default")
      (node (ref "C411") (pin "1") (pinfunction "1_1") (pintype "passive"))
      (node (ref "R411") (pin "2") (pinfunction "2_2") (pintype "passive"))
      (node (ref "R412") (pin "2") (pinfunction "2_2") (pintype "passive"))
      (node (ref "U5") (pin "3") (pinfunction "+IN_3") (pintype "input"))
    )
    (net (code "62") (name "Net-(U5--IN)") (class "Default")
      (node (ref "R501") (pin "2") (pinfunction "2_2") (pintype "passive"))
      (node (ref "U5") (pin "4") (pinfunction "-IN_4") (pintype "input"))
    )
    (net (code "63") (name "PHASE_ERROR") (class "Default")
      (node (ref "D401") (pin "C") (pinfunction "C_C") (pintype "passive"))
      (node (ref "R411") (pin "1") (pinfunction "1_1") (pintype "passive"))
    )
    (net (code "64") (name "PHASE_RSFF") (class "Default")
      (node (ref "D401") (pin "A") (pinfunction "A_A") (pintype "passive"))
      (node (ref "IC2") (pin "35") (pinfunction "IOB12_35") (pintype "bidirectional"))
    )
    (net (code "65") (name "SYNC_IN") (class "Default")
      (node (ref "IC2") (pin "37") (pinfunction "IOB14_37") (pintype "bidirectional"))
      (node (ref "IC3") (pin "13") (pinfunction "Q_13") (pintype "output"))
    )
    (net (code "66") (name "VCC") (class "Default")
      (node (ref "C191") (pin "1") (pinfunction "1_1") (pintype "passive"))
      (node (ref "C211") (pin "1") (pinfunction "1_1") (pintype "passive"))
      (node (ref "C391") (pin "1") (pinfunction "1_1") (pintype "passive"))
      (node (ref "C491") (pin "1") (pinfunction "1_1") (pintype "passive"))
      (node (ref "C591") (pin "1") (pinfunction "1_1") (pintype "passive"))
      (node (ref "C911") (pin "1") (pinfunction "1_1") (pintype "passive"))
      (node (ref "C912") (pin "1") (pinfunction "1_1") (pintype "passive"))
      (node (ref "CON5") (pin "7") (pinfunction "7_7") (pintype "passive"))
      (node (ref "CON6") (pin "3") (pinfunction "3_3") (pintype "passive"))
      (node (ref "IC1") (pin "7") (pinfunction "VCC_7") (pintype "bidirectional"))
      (node (ref "IC3") (pin "10") (pinfunction "B_10") (pintype "input"))
      (node (ref "IC3") (pin "11") (pinfunction "R_11") (pintype "input"))
      (node (ref "IC3") (pin "16") (pinfunction "VCC_16") (pintype "power_in"))
      (node (ref "IC3") (pin "2") (pinfunction "B_2") (pintype "input"))
      (node (ref "IC3") (pin "3") (pinfunction "R_3") (pintype "input"))
      (node (ref "IC6") (pin "5") (pinfunction "VIN_5") (pintype "power_in"))
      (node (ref "JP941") (pin "1") (pinfunction "1_1") (pintype "passive"))
      (node (ref "L101") (pin "2") (pinfunction "2_2") (pintype "passive"))
      (node (ref "R111") (pin "1") (pinfunction "1_1") (pintype "passive"))
      (node (ref "R132") (pin "2") (pinfunction "2_2") (pintype "passive"))
      (node (ref "R301") (pin "2") (pinfunction "2_2") (pintype "passive"))
      (node (ref "R311") (pin "2") (pinfunction "2_2") (pintype "passive"))
      (node (ref "R601") (pin "1") (pinfunction "1_1") (pintype "passive"))
      (node (ref "R951") (pin "2") (pinfunction "2_2") (pintype "passive"))
      (node (ref "RPOLY1") (pin "2") (pinfunction "2_2") (pintype "passive"))
      (node (ref "U5") (pin "5") (pinfunction "V+_5") (pintype "power_in"))
    )
    (net (code "67") (name "unconnected-(CON5-Pad8)") (class "Default")
      (node (ref "CON5") (pin "8") (pinfunction "8_8") (pintype "passive"))
    )
    (net (code "68") (name "unconnected-(IC1-PB7(XTAL2{slash}TOSC2)-Pad10)") (class "Default")
      (node (ref "IC1") (pin "10") (pinfunction "PB7(XTAL2/TOSC2)_10") (pintype "bidirectional"))
    )
    (net (code "69") (name "unconnected-(IC2-IOA1-Pad41)") (class "Default")
      (node (ref "IC2") (pin "41") (pinfunction "IOA1_41") (pintype "bidirectional"))
    )
    (net (code "70") (name "unconnected-(IC2-IOA5-Pad2)") (class "Default")
      (node (ref "IC2") (pin "2") (pinfunction "IOA5_2") (pintype "bidirectional"))
    )
    (net (code "71") (name "unconnected-(IC2-IOA6-Pad3)") (class "Default")
      (node (ref "IC2") (pin "3") (pinfunction "IOA6_3") (pintype "bidirectional"))
    )
    (net (code "72") (name "unconnected-(IC2-IOA13-Pad14)") (class "Default")
      (node (ref "IC2") (pin "14") (pinfunction "IOA13_14") (pintype "bidirectional"))
    )
    (net (code "73") (name "unconnected-(IC2-IOA14-Pad15)") (class "Default")
      (node (ref "IC2") (pin "15") (pinfunction "IOA14_15") (pintype "bidirectional"))
    )
    (net (code "74") (name "unconnected-(IC2-IOB0-Pad18)") (class "Default")
      (node (ref "IC2") (pin "18") (pinfunction "IOB0_18") (pintype "bidirectional"))
    )
    (net (code "75") (name "unconnected-(IC2-IOB1-Pad19)") (class "Default")
      (node (ref "IC2") (pin "19") (pinfunction "IOB1_19") (pintype "bidirectional"))
    )
    (net (code "76") (name "unconnected-(IC2-IOB2-Pad20)") (class "Default")
      (node (ref "IC2") (pin "20") (pinfunction "IOB2_20") (pintype "bidirectional"))
    )
    (net (code "77") (name "unconnected-(IC2-IOB3-Pad21)") (class "Default")
      (node (ref "IC2") (pin "21") (pinfunction "IOB3_21") (pintype "bidirectional"))
    )
    (net (code "78") (name "unconnected-(IC2-IOB4-Pad22)") (class "Default")
      (node (ref "IC2") (pin "22") (pinfunction "IOB4_22") (pintype "bidirectional"))
    )
    (net (code "79") (name "unconnected-(IC2-IOB5-Pad24)") (class "Default")
      (node (ref "IC2") (pin "24") (pinfunction "IOB5_24") (pintype "bidirectional"))
    )
    (net (code "80") (name "unconnected-(IC2-IOB6-Pad25)") (class "Default")
      (node (ref "IC2") (pin "25") (pinfunction "IOB6_25") (pintype "bidirectional"))
    )
    (net (code "81") (name "unconnected-(IC2-IOB7-Pad26)") (class "Default")
      (node (ref "IC2") (pin "26") (pinfunction "IOB7_26") (pintype "bidirectional"))
    )
    (net (code "82") (name "unconnected-(IC2-IOB8-Pad29)") (class "Default")
      (node (ref "IC2") (pin "29") (pinfunction "IOB8_29") (pintype "bidirectional"))
    )
    (net (code "83") (name "unconnected-(IC2-IOB9-Pad30)") (class "Default")
      (node (ref "IC2") (pin "30") (pinfunction "IOB9_30") (pintype "bidirectional"))
    )
    (net (code "84") (name "unconnected-(IC3A-~{Q}-Pad4)") (class "Default")
      (node (ref "IC3") (pin "4") (pinfunction "~{Q}_4") (pintype "output"))
    )
    (net (code "85") (name "unconnected-(IC3B-~{Q}-Pad12)") (class "Default")
      (node (ref "IC3") (pin "12") (pinfunction "~{Q}_12") (pintype "output"))
    )
    (net (code "86") (name "unconnected-(IC8-Pad5)") (class "Default")
      (node (ref "IC8") (pin "5") (pinfunction "5_5") (pintype "no_connect"))
    )
    (net (code "87") (name "unconnected-(IC8-Pad7)") (class "Default")
      (node (ref "IC8") (pin "7") (pinfunction "7_7") (pintype "bidirectional"))
    )
    (net (code "88") (name "unconnected-(IC8-Pad9)") (class "Default")
      (node (ref "IC8") (pin "9") (pinfunction "9_9") (pintype "no_connect"))
    )
    (net (code "89") (name "unconnected-(IC8-Pad13)") (class "Default")
      (node (ref "IC8") (pin "13") (pinfunction "13_13") (pintype "no_connect"))
    )
    (net (code "90") (name "unconnected-(IC8-Pad15)") (class "Default")
      (node (ref "IC8") (pin "15") (pinfunction "15_15") (pintype "no_connect"))
    )
    (net (code "91") (name "unconnected-(IC8-Pad16)") (class "Default")
      (node (ref "IC8") (pin "16") (pinfunction "16_16") (pintype "no_connect"))
    )
    (net (code "92") (name "unconnected-(IC8-Pad17)") (class "Default")
      (node (ref "IC8") (pin "17") (pinfunction "17_17") (pintype "no_connect"))
    )
    (net (code "93") (name "unconnected-(IC8-Pad18)") (class "Default")
      (node (ref "IC8") (pin "18") (pinfunction "18_18") (pintype "no_connect"))
    )
  )
)
